# LabPower-FB_MC.net
KiCad netlist of a schematic drawn in EAGLE
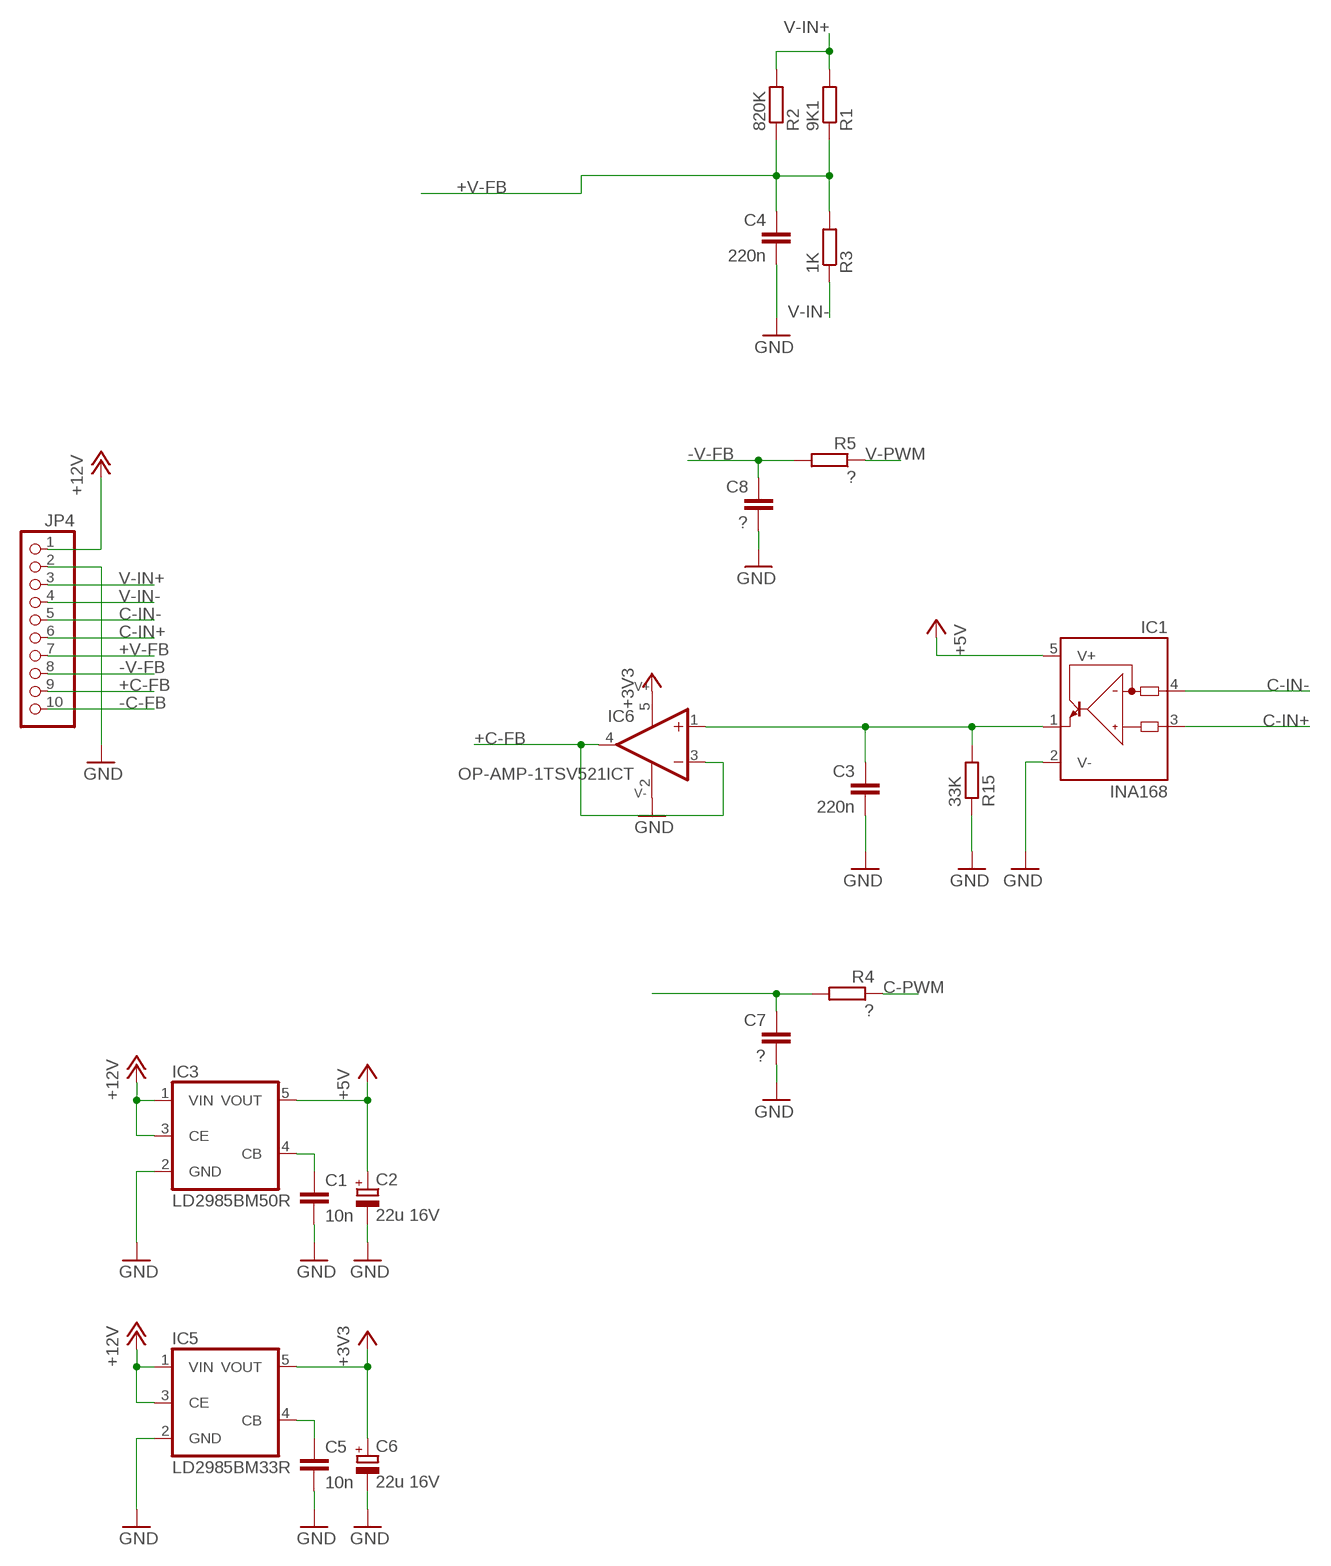
[diagram p0: schematic, sheet 1]
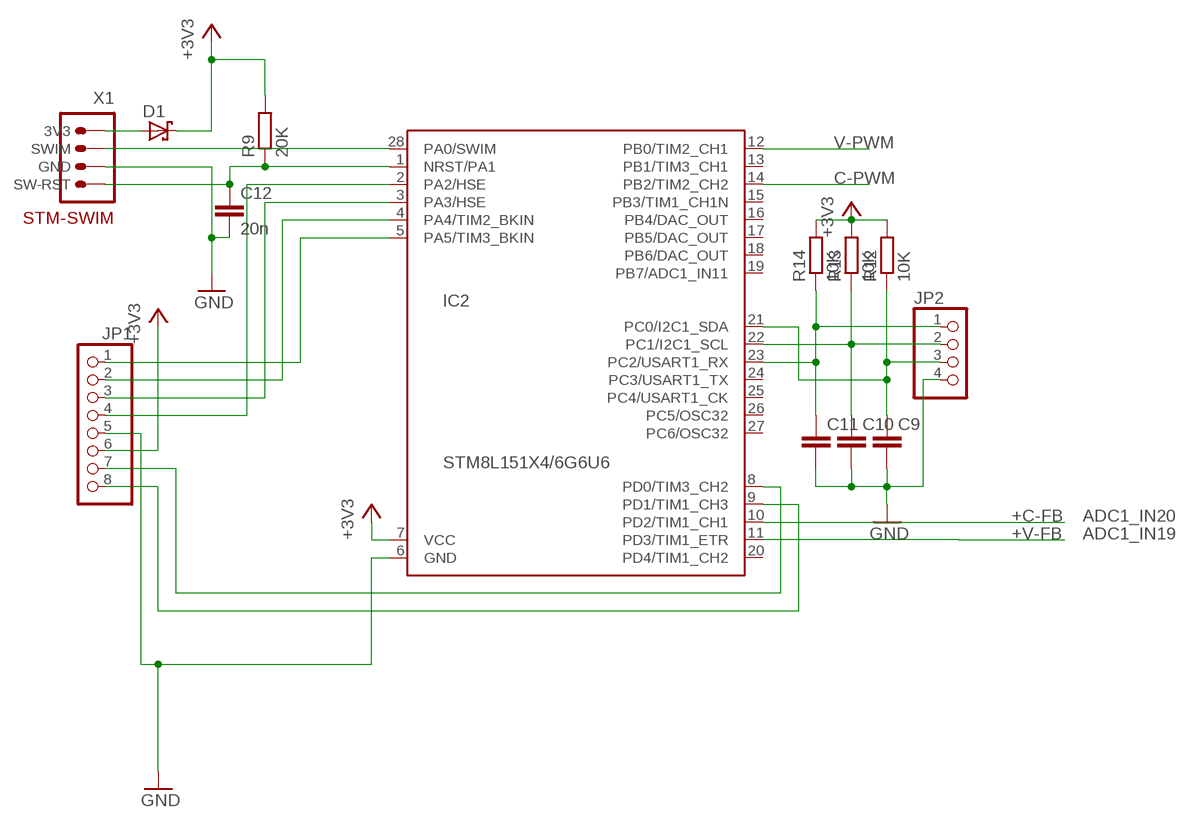
[diagram p1: schematic, sheet 2]

(export (version "E")
  (design (tool "Eeschema 10.0.6"))
  (components
    (comp (ref "C1")
      (value "10n")
      (footprint "eagle-import:C0805")
      (libsource (lib "eagle-import") (part "C-EUC0805"))
    )
    (comp (ref "C2")
      (value "22u 16V")
      (footprint "eagle-import:B_3528-21W")
      (libsource (lib "eagle-import") (part "CPOL-EUB/3528-21W"))
    )
    (comp (ref "C3")
      (value "220n")
      (footprint "eagle-import:C0805")
      (libsource (lib "eagle-import") (part "CAP_0805"))
    )
    (comp (ref "C4")
      (value "220n")
      (footprint "eagle-import:C0805")
      (libsource (lib "eagle-import") (part "CAP_0805"))
    )
    (comp (ref "C5")
      (value "10n")
      (footprint "eagle-import:C0805")
      (libsource (lib "eagle-import") (part "C-EUC0805"))
    )
    (comp (ref "C6")
      (value "22u 16V")
      (footprint "eagle-import:B_3528-21W")
      (libsource (lib "eagle-import") (part "CPOL-EUB/3528-21W"))
    )
    (comp (ref "C7")
      (value "?")
      (footprint "eagle-import:C0805")
      (libsource (lib "eagle-import") (part "CAP_0805"))
    )
    (comp (ref "C8")
      (value "?")
      (footprint "eagle-import:C0805")
      (libsource (lib "eagle-import") (part "CAP_0805"))
    )
    (comp (ref "IC1")
      (value "INA168")
      (footprint "eagle-import:SOT23-5")
      (fields (field (name "MF") "TEXAS INSTRUMENTS") (field (name "MPN") "INA168NA/250"))
      (libsource (lib "eagle-import") (part "INA168"))
    )
    (comp (ref "IC3")
      (value "LD2985BM50R")
      (footprint "eagle-import:SOT25")
      (libsource (lib "eagle-import") (part "TS5205"))
    )
    (comp (ref "IC5")
      (value "LD2985BM33R")
      (footprint "eagle-import:SOT25")
      (libsource (lib "eagle-import") (part "TS5205"))
    )
    (comp (ref "IC6")
      (value "OP-AMP-1TSV521ICT")
      (footprint "eagle-import:SC70-5L")
      (libsource (lib "eagle-import") (part "OP-AMP-1TSV521ICT"))
    )
    (comp (ref "JP4")
      (value "PINHD-1X10/90")
      (footprint "eagle-import:1X10_90")
      (libsource (lib "eagle-import") (part "PINHD-1X10/90"))
    )
    (comp (ref "R1")
      (value "9K1")
      (footprint "eagle-import:R0805")
      (libsource (lib "eagle-import") (part "R-EU_R0805"))
    )
    (comp (ref "R2")
      (value "820K")
      (footprint "eagle-import:R0805")
      (libsource (lib "eagle-import") (part "R-EU_R0805"))
    )
    (comp (ref "R3")
      (value "1K")
      (footprint "eagle-import:R0805")
      (libsource (lib "eagle-import") (part "R-EU_R0805"))
    )
    (comp (ref "R4")
      (value "?")
      (footprint "eagle-import:R0805")
      (libsource (lib "eagle-import") (part "R_0805"))
    )
    (comp (ref "R5")
      (value "?")
      (footprint "eagle-import:R0805")
      (libsource (lib "eagle-import") (part "R_0805"))
    )
    (comp (ref "R15")
      (value "33K")
      (footprint "eagle-import:R0805")
      (libsource (lib "eagle-import") (part "R-EU_R0805"))
    )
    (comp (ref "C9")
      (value "CAP_0805")
      (footprint "eagle-import:C0805")
      (libsource (lib "eagle-import") (part "CAP_0805"))
    )
    (comp (ref "C10")
      (value "CAP_0805")
      (footprint "eagle-import:C0805")
      (libsource (lib "eagle-import") (part "CAP_0805"))
    )
    (comp (ref "C11")
      (value "CAP_0805")
      (footprint "eagle-import:C0805")
      (libsource (lib "eagle-import") (part "CAP_0805"))
    )
    (comp (ref "C12")
      (value "20n")
      (footprint "eagle-import:C0805")
      (libsource (lib "eagle-import") (part "CAP_0805"))
    )
    (comp (ref "D1")
      (value "DIODE-SH_SOD523")
      (footprint "eagle-import:SOD523")
      (libsource (lib "eagle-import") (part "DIODE-SH_SOD523"))
    )
    (comp (ref "IC2")
      (value "STM8L151X4/6G6U6")
      (footprint "eagle-import:QFN28")
      (libsource (lib "eagle-import") (part "STM8L151X4/6G6U6"))
    )
    (comp (ref "JP1")
      (value "PINHD-1X8")
      (footprint "eagle-import:1X08")
      (libsource (lib "eagle-import") (part "PINHD-1X8"))
    )
    (comp (ref "JP2")
      (value "PINHD-1X4")
      (footprint "eagle-import:1X04")
      (libsource (lib "eagle-import") (part "PINHD-1X4"))
    )
    (comp (ref "R9")
      (value "20K")
      (footprint "eagle-import:R0805")
      (libsource (lib "eagle-import") (part "R_0805"))
    )
    (comp (ref "R12")
      (value "10K")
      (footprint "eagle-import:R0805")
      (libsource (lib "eagle-import") (part "R_0805"))
    )
    (comp (ref "R13")
      (value "10K")
      (footprint "eagle-import:R0805")
      (libsource (lib "eagle-import") (part "R_0805"))
    )
    (comp (ref "R14")
      (value "10K")
      (footprint "eagle-import:R0805")
      (libsource (lib "eagle-import") (part "R_0805"))
    )
    (comp (ref "X1")
      (value "STM-SWIMPINS")
      (footprint "eagle-import:1X04_90")
      (libsource (lib "eagle-import") (part "STM-SWIMPINS"))
    )
  )
  (nets
    (net (code "1") (name "+3V3") (class "Default")
      (node (ref "C6") (pin "+") (pinfunction "+_+") (pintype "passive"))
      (node (ref "D1") (pin "C") (pinfunction "C_C") (pintype "passive"))
      (node (ref "IC2") (pin "7") (pinfunction "VCC_7") (pintype "power_in"))
      (node (ref "IC5") (pin "5") (pinfunction "VOUT_5") (pintype "passive"))
      (node (ref "IC6") (pin "5") (pinfunction "V+_5") (pintype "power_in"))
      (node (ref "JP1") (pin "6") (pinfunction "6_6") (pintype "passive"))
      (node (ref "R12") (pin "2") (pinfunction "2_2") (pintype "passive"))
      (node (ref "R13") (pin "2") (pinfunction "2_2") (pintype "passive"))
      (node (ref "R14") (pin "2") (pinfunction "2_2") (pintype "passive"))
      (node (ref "R9") (pin "2") (pinfunction "2_2") (pintype "passive"))
    )
    (net (code "2") (name "+5V") (class "Default")
      (node (ref "C2") (pin "+") (pinfunction "+_+") (pintype "passive"))
      (node (ref "IC1") (pin "5") (pinfunction "V+_5") (pintype "power_in"))
      (node (ref "IC3") (pin "5") (pinfunction "VOUT_5") (pintype "passive"))
    )
    (net (code "3") (name "+12V") (class "Default")
      (node (ref "IC3") (pin "1") (pinfunction "VIN_1") (pintype "input"))
      (node (ref "IC3") (pin "3") (pinfunction "CE_3") (pintype "input"))
      (node (ref "IC5") (pin "1") (pinfunction "VIN_1") (pintype "input"))
      (node (ref "IC5") (pin "3") (pinfunction "CE_3") (pintype "input"))
      (node (ref "JP4") (pin "1") (pinfunction "1_1") (pintype "passive"))
    )
    (net (code "4") (name "+C-FB") (class "Default")
      (node (ref "IC2") (pin "10") (pinfunction "PD2/TIM1_CH1_10") (pintype "bidirectional"))
      (node (ref "IC6") (pin "3") (pinfunction "-IN_3") (pintype "input"))
      (node (ref "IC6") (pin "4") (pinfunction "OUT_4") (pintype "output"))
      (node (ref "JP4") (pin "9") (pinfunction "9_9") (pintype "passive"))
    )
    (net (code "5") (name "+V-FB") (class "Default")
      (node (ref "C4") (pin "1") (pinfunction "1_1") (pintype "passive"))
      (node (ref "IC2") (pin "11") (pinfunction "PD3/TIM1_ETR_11") (pintype "bidirectional"))
      (node (ref "JP4") (pin "7") (pinfunction "7_7") (pintype "passive"))
      (node (ref "R1") (pin "1") (pinfunction "1_1") (pintype "passive"))
      (node (ref "R2") (pin "1") (pinfunction "1_1") (pintype "passive"))
      (node (ref "R3") (pin "2") (pinfunction "2_2") (pintype "passive"))
    )
    (net (code "6") (name "-C-FB") (class "Default")
      (node (ref "C7") (pin "1") (pinfunction "1_1") (pintype "passive"))
      (node (ref "JP4") (pin "10") (pinfunction "10_10") (pintype "passive"))
      (node (ref "R4") (pin "2") (pinfunction "2_2") (pintype "passive"))
    )
    (net (code "7") (name "-V-FB") (class "Default")
      (node (ref "C8") (pin "1") (pinfunction "1_1") (pintype "passive"))
      (node (ref "JP4") (pin "8") (pinfunction "8_8") (pintype "passive"))
      (node (ref "R5") (pin "2") (pinfunction "2_2") (pintype "passive"))
    )
    (net (code "8") (name "C-IN+") (class "Default")
      (node (ref "IC1") (pin "3") (pinfunction "IN+_3") (pintype "input"))
      (node (ref "JP4") (pin "6") (pinfunction "6_6") (pintype "passive"))
    )
    (net (code "9") (name "C-IN-") (class "Default")
      (node (ref "IC1") (pin "4") (pinfunction "IN-_4") (pintype "input"))
      (node (ref "JP4") (pin "5") (pinfunction "5_5") (pintype "passive"))
    )
    (net (code "10") (name "C-PWM") (class "Default")
      (node (ref "IC2") (pin "14") (pinfunction "PB2/TIM2_CH2_14") (pintype "bidirectional"))
      (node (ref "R4") (pin "1") (pinfunction "1_1") (pintype "passive"))
    )
    (net (code "11") (name "GND") (class "Default")
      (node (ref "C1") (pin "2") (pinfunction "2_2") (pintype "passive"))
      (node (ref "C10") (pin "2") (pinfunction "2_2") (pintype "passive"))
      (node (ref "C11") (pin "2") (pinfunction "2_2") (pintype "passive"))
      (node (ref "C12") (pin "2") (pinfunction "2_2") (pintype "passive"))
      (node (ref "C2") (pin "-") (pinfunction "-_-") (pintype "passive"))
      (node (ref "C3") (pin "2") (pinfunction "2_2") (pintype "passive"))
      (node (ref "C4") (pin "2") (pinfunction "2_2") (pintype "passive"))
      (node (ref "C5") (pin "2") (pinfunction "2_2") (pintype "passive"))
      (node (ref "C6") (pin "-") (pinfunction "-_-") (pintype "passive"))
      (node (ref "C7") (pin "2") (pinfunction "2_2") (pintype "passive"))
      (node (ref "C8") (pin "2") (pinfunction "2_2") (pintype "passive"))
      (node (ref "C9") (pin "2") (pinfunction "2_2") (pintype "passive"))
      (node (ref "IC1") (pin "2") (pinfunction "V-_2") (pintype "power_in"))
      (node (ref "IC2") (pin "6") (pinfunction "GND_6") (pintype "power_in"))
      (node (ref "IC3") (pin "2") (pinfunction "GND_2") (pintype "passive"))
      (node (ref "IC5") (pin "2") (pinfunction "GND_2") (pintype "passive"))
      (node (ref "IC6") (pin "2") (pinfunction "V-_2") (pintype "power_in"))
      (node (ref "JP1") (pin "5") (pinfunction "5_5") (pintype "passive"))
      (node (ref "JP2") (pin "4") (pinfunction "4_4") (pintype "passive"))
      (node (ref "JP4") (pin "2") (pinfunction "2_2") (pintype "passive"))
      (node (ref "R15") (pin "1") (pinfunction "1_1") (pintype "passive"))
      (node (ref "X1") (pin "3") (pinfunction "GND_3") (pintype "passive"))
    )
    (net (code "12") (name "Net-(IC1-OUT)") (class "Default")
      (node (ref "C3") (pin "1") (pinfunction "1_1") (pintype "passive"))
      (node (ref "IC1") (pin "1") (pinfunction "OUT_1") (pintype "output"))
      (node (ref "IC6") (pin "1") (pinfunction "+IN_1") (pintype "input"))
      (node (ref "R15") (pin "2") (pinfunction "2_2") (pintype "passive"))
    )
    (net (code "13") (name "Net-(IC2-NRST{slash}PA1)") (class "Default")
      (node (ref "C12") (pin "1") (pinfunction "1_1") (pintype "passive"))
      (node (ref "IC2") (pin "1") (pinfunction "NRST/PA1_1") (pintype "bidirectional"))
      (node (ref "R9") (pin "1") (pinfunction "1_1") (pintype "passive"))
      (node (ref "X1") (pin "4") (pinfunction "SW-RST_4") (pintype "passive"))
    )
    (net (code "14") (name "Net-(IC2-PA0{slash}SWIM)") (class "Default")
      (node (ref "IC2") (pin "28") (pinfunction "PA0/SWIM_28") (pintype "bidirectional"))
      (node (ref "X1") (pin "2") (pinfunction "SWIM_2") (pintype "passive"))
    )
    (net (code "15") (name "Net-(IC2-PA2{slash}HSE)") (class "Default")
      (node (ref "IC2") (pin "2") (pinfunction "PA2/HSE_2") (pintype "bidirectional"))
      (node (ref "JP1") (pin "4") (pinfunction "4_4") (pintype "passive"))
    )
    (net (code "16") (name "Net-(IC2-PA3{slash}HSE)") (class "Default")
      (node (ref "IC2") (pin "3") (pinfunction "PA3/HSE_3") (pintype "bidirectional"))
      (node (ref "JP1") (pin "3") (pinfunction "3_3") (pintype "passive"))
    )
    (net (code "17") (name "Net-(IC2-PA4{slash}TIM2_BKIN)") (class "Default")
      (node (ref "IC2") (pin "4") (pinfunction "PA4/TIM2_BKIN_4") (pintype "bidirectional"))
      (node (ref "JP1") (pin "2") (pinfunction "2_2") (pintype "passive"))
    )
    (net (code "18") (name "Net-(IC2-PA5{slash}TIM3_BKIN)") (class "Default")
      (node (ref "IC2") (pin "5") (pinfunction "PA5/TIM3_BKIN_5") (pintype "bidirectional"))
      (node (ref "JP1") (pin "1") (pinfunction "1_1") (pintype "passive"))
    )
    (net (code "19") (name "Net-(IC2-PC0{slash}I2C1_SDA)") (class "Default")
      (node (ref "C9") (pin "1") (pinfunction "1_1") (pintype "passive"))
      (node (ref "IC2") (pin "21") (pinfunction "PC0/I2C1_SDA_21") (pintype "bidirectional"))
      (node (ref "JP2") (pin "3") (pinfunction "3_3") (pintype "passive"))
      (node (ref "R12") (pin "1") (pinfunction "1_1") (pintype "passive"))
    )
    (net (code "20") (name "Net-(IC2-PC1{slash}I2C1_SCL)") (class "Default")
      (node (ref "C10") (pin "1") (pinfunction "1_1") (pintype "passive"))
      (node (ref "IC2") (pin "22") (pinfunction "PC1/I2C1_SCL_22") (pintype "bidirectional"))
      (node (ref "JP2") (pin "2") (pinfunction "2_2") (pintype "passive"))
      (node (ref "R13") (pin "1") (pinfunction "1_1") (pintype "passive"))
    )
    (net (code "21") (name "Net-(IC2-PC2{slash}USART1_RX)") (class "Default")
      (node (ref "C11") (pin "1") (pinfunction "1_1") (pintype "passive"))
      (node (ref "IC2") (pin "23") (pinfunction "PC2/USART1_RX_23") (pintype "bidirectional"))
      (node (ref "JP2") (pin "1") (pinfunction "1_1") (pintype "passive"))
      (node (ref "R14") (pin "1") (pinfunction "1_1") (pintype "passive"))
    )
    (net (code "22") (name "Net-(IC2-PD0{slash}TIM3_CH2)") (class "Default")
      (node (ref "IC2") (pin "8") (pinfunction "PD0/TIM3_CH2_8") (pintype "bidirectional"))
      (node (ref "JP1") (pin "7") (pinfunction "7_7") (pintype "passive"))
    )
    (net (code "23") (name "Net-(IC2-PD1{slash}TIM1_CH3)") (class "Default")
      (node (ref "IC2") (pin "9") (pinfunction "PD1/TIM1_CH3_9") (pintype "bidirectional"))
      (node (ref "JP1") (pin "8") (pinfunction "8_8") (pintype "passive"))
    )
    (net (code "24") (name "Net-(IC3-CB)") (class "Default")
      (node (ref "C1") (pin "1") (pinfunction "1_1") (pintype "passive"))
      (node (ref "IC3") (pin "4") (pinfunction "CB_4") (pintype "input"))
    )
    (net (code "25") (name "Net-(IC5-CB)") (class "Default")
      (node (ref "C5") (pin "1") (pinfunction "1_1") (pintype "passive"))
      (node (ref "IC5") (pin "4") (pinfunction "CB_4") (pintype "input"))
    )
    (net (code "26") (name "Net-(X1-3V3)") (class "Default")
      (node (ref "D1") (pin "A") (pinfunction "A_A") (pintype "passive"))
      (node (ref "X1") (pin "1") (pinfunction "3V3_1") (pintype "passive"))
    )
    (net (code "27") (name "V-IN+") (class "Default")
      (node (ref "JP4") (pin "3") (pinfunction "3_3") (pintype "passive"))
      (node (ref "R1") (pin "2") (pinfunction "2_2") (pintype "passive"))
      (node (ref "R2") (pin "2") (pinfunction "2_2") (pintype "passive"))
    )
    (net (code "28") (name "V-IN-") (class "Default")
      (node (ref "JP4") (pin "4") (pinfunction "4_4") (pintype "passive"))
      (node (ref "R3") (pin "1") (pinfunction "1_1") (pintype "passive"))
    )
    (net (code "29") (name "V-PWM") (class "Default")
      (node (ref "IC2") (pin "12") (pinfunction "PB0/TIM2_CH1_12") (pintype "bidirectional"))
      (node (ref "R5") (pin "1") (pinfunction "1_1") (pintype "passive"))
    )
    (net (code "30") (name "unconnected-(IC2-PB1{slash}TIM3_CH1-Pad13)") (class "Default")
      (node (ref "IC2") (pin "13") (pinfunction "PB1/TIM3_CH1_13") (pintype "bidirectional"))
    )
    (net (code "31") (name "unconnected-(IC2-PB3{slash}TIM1_CH1N-Pad15)") (class "Default")
      (node (ref "IC2") (pin "15") (pinfunction "PB3/TIM1_CH1N_15") (pintype "bidirectional"))
    )
    (net (code "32") (name "unconnected-(IC2-PB4{slash}DAC_OUT-Pad16)") (class "Default")
      (node (ref "IC2") (pin "16") (pinfunction "PB4/DAC_OUT_16") (pintype "bidirectional"))
    )
    (net (code "33") (name "unconnected-(IC2-PB5{slash}DAC_OUT-Pad17)") (class "Default")
      (node (ref "IC2") (pin "17") (pinfunction "PB5/DAC_OUT_17") (pintype "bidirectional"))
    )
    (net (code "34") (name "unconnected-(IC2-PB6{slash}DAC_OUT-Pad18)") (class "Default")
      (node (ref "IC2") (pin "18") (pinfunction "PB6/DAC_OUT_18") (pintype "bidirectional"))
    )
    (net (code "35") (name "unconnected-(IC2-PB7{slash}ADC1_IN11-Pad19)") (class "Default")
      (node (ref "IC2") (pin "19") (pinfunction "PB7/ADC1_IN11_19") (pintype "bidirectional"))
    )
    (net (code "36") (name "unconnected-(IC2-PC3{slash}USART1_TX-Pad24)") (class "Default")
      (node (ref "IC2") (pin "24") (pinfunction "PC3/USART1_TX_24") (pintype "bidirectional"))
    )
    (net (code "37") (name "unconnected-(IC2-PC4{slash}USART1_CK-Pad25)") (class "Default")
      (node (ref "IC2") (pin "25") (pinfunction "PC4/USART1_CK_25") (pintype "bidirectional"))
    )
    (net (code "38") (name "unconnected-(IC2-PC5{slash}OSC32-Pad26)") (class "Default")
      (node (ref "IC2") (pin "26") (pinfunction "PC5/OSC32_26") (pintype "bidirectional"))
    )
    (net (code "39") (name "unconnected-(IC2-PC6{slash}OSC32-Pad27)") (class "Default")
      (node (ref "IC2") (pin "27") (pinfunction "PC6/OSC32_27") (pintype "bidirectional"))
    )
    (net (code "40") (name "unconnected-(IC2-PD4{slash}TIM1_CH2-Pad20)") (class "Default")
      (node (ref "IC2") (pin "20") (pinfunction "PD4/TIM1_CH2_20") (pintype "bidirectional"))
    )
  )
)
